# cell.net
KiCad netlist of a schematic drawn in EAGLE
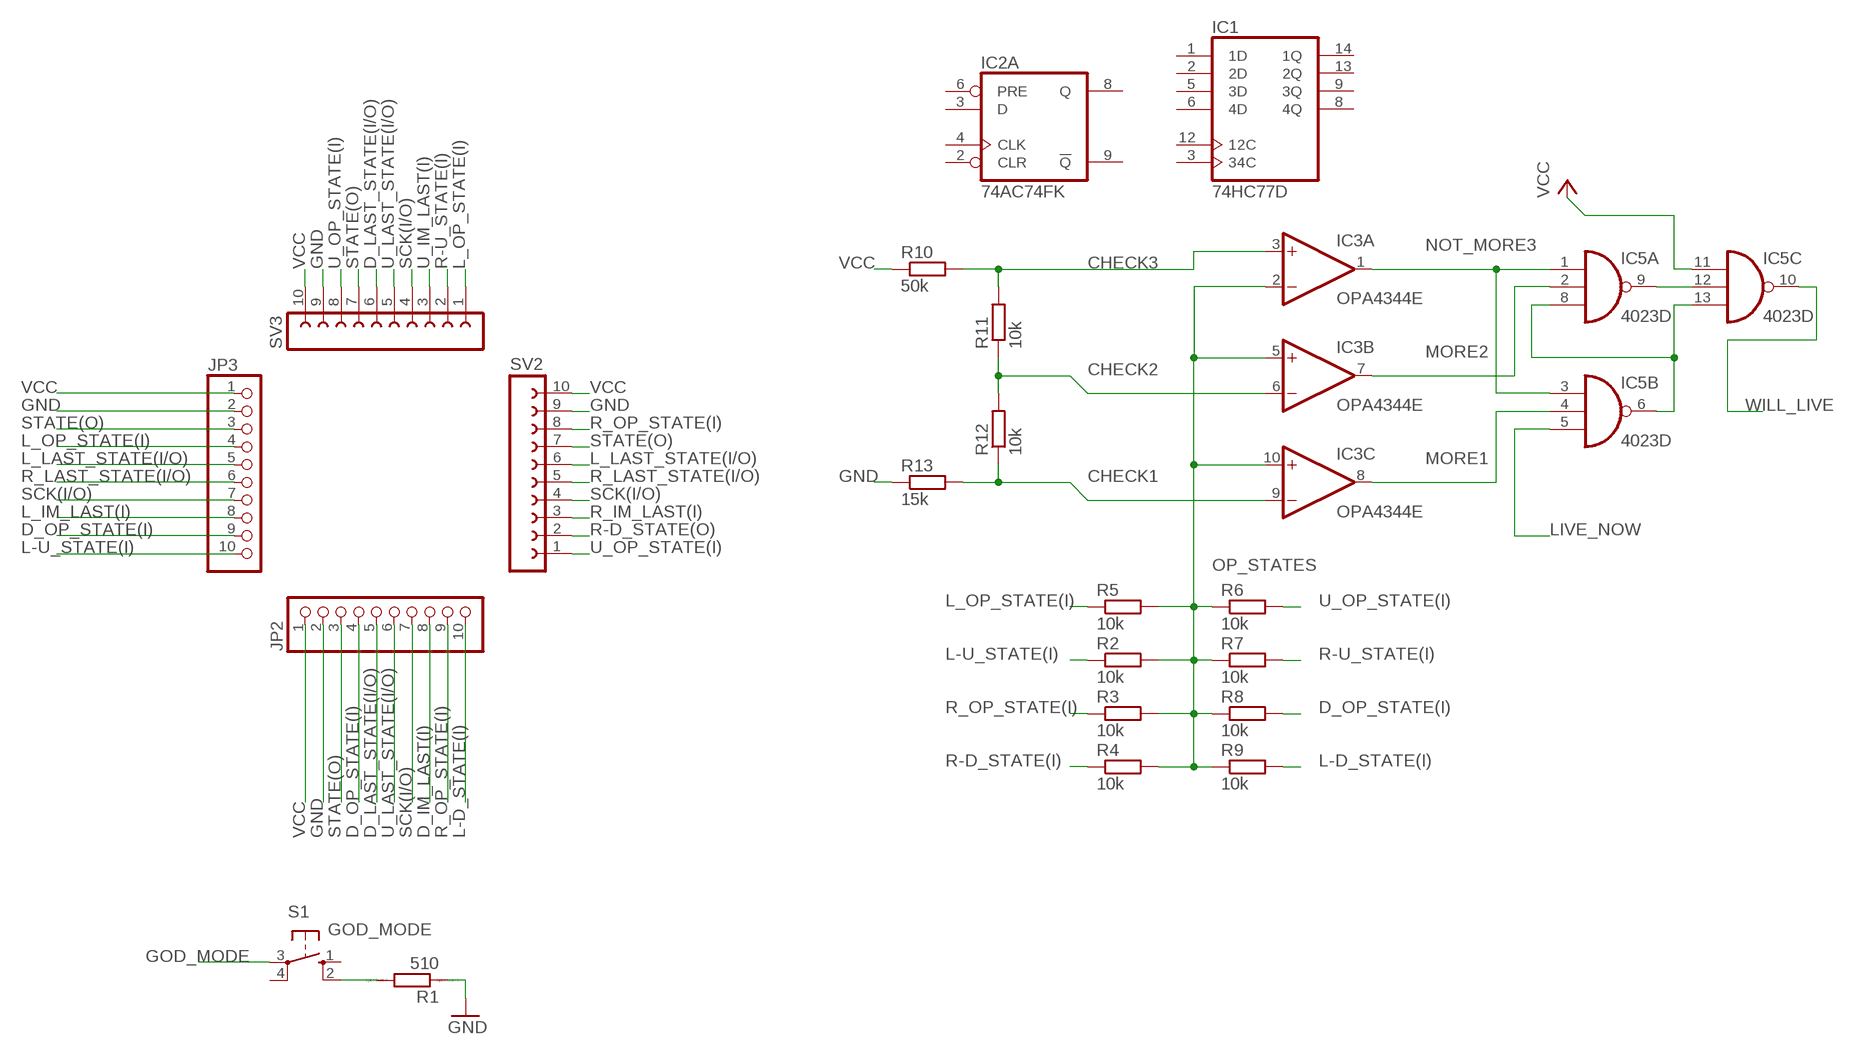
[diagram p0: schematic, sheet 1]

(export (version "E")
  (design (tool "Eeschema 10.0.6"))
  (components
    (comp (ref "IC1")
      (value "74HC77D")
      (footprint "eagle-import:SO14")
      (libsource (lib "eagle-import") (part "7477DHC"))
    )
    (comp (ref "IC2")
      (value "74AC74FK")
      (footprint "eagle-import:LCC20")
      (libsource (lib "eagle-import") (part "7474FKAC"))
    )
    (comp (ref "IC3")
      (value "OPA4344E")
      (footprint "eagle-import:TSSOP14")
      (libsource (lib "eagle-import") (part "OPA4E344"))
    )
    (comp (ref "IC5")
      (value "4023D")
      (footprint "eagle-import:SO14")
      (libsource (lib "eagle-import") (part "4023D"))
    )
    (comp (ref "JP2")
      (value "PINHD-1X10")
      (footprint "eagle-import:1X10")
      (libsource (lib "eagle-import") (part "PINHD-1X10"))
    )
    (comp (ref "JP3")
      (value "PINHD-1X10")
      (footprint "eagle-import:1X10")
      (libsource (lib "eagle-import") (part "PINHD-1X10"))
    )
    (comp (ref "R1")
      (value "510")
      (footprint "eagle-import:R0805")
      (libsource (lib "eagle-import") (part "R"))
    )
    (comp (ref "R2")
      (value "10k")
      (footprint "eagle-import:R0805")
      (libsource (lib "eagle-import") (part "R-EU_R0805"))
    )
    (comp (ref "R3")
      (value "10k")
      (footprint "eagle-import:R0805")
      (libsource (lib "eagle-import") (part "R-EU_R0805"))
    )
    (comp (ref "R4")
      (value "10k")
      (footprint "eagle-import:R0805")
      (libsource (lib "eagle-import") (part "R-EU_R0805"))
    )
    (comp (ref "R5")
      (value "10k")
      (footprint "eagle-import:R0805")
      (libsource (lib "eagle-import") (part "R-EU_R0805"))
    )
    (comp (ref "R6")
      (value "10k")
      (footprint "eagle-import:R0805")
      (libsource (lib "eagle-import") (part "R-EU_R0805"))
    )
    (comp (ref "R7")
      (value "10k")
      (footprint "eagle-import:R0805")
      (libsource (lib "eagle-import") (part "R-EU_R0805"))
    )
    (comp (ref "R8")
      (value "10k")
      (footprint "eagle-import:R0805")
      (libsource (lib "eagle-import") (part "R-EU_R0805"))
    )
    (comp (ref "R9")
      (value "10k")
      (footprint "eagle-import:R0805")
      (libsource (lib "eagle-import") (part "R-EU_R0805"))
    )
    (comp (ref "R10")
      (value "50k")
      (footprint "eagle-import:R0805")
      (libsource (lib "eagle-import") (part "R-EU_R0805"))
    )
    (comp (ref "R11")
      (value "10k")
      (footprint "eagle-import:R0805")
      (libsource (lib "eagle-import") (part "R-EU_R0805"))
    )
    (comp (ref "R12")
      (value "10k")
      (footprint "eagle-import:R0805")
      (libsource (lib "eagle-import") (part "R-EU_R0805"))
    )
    (comp (ref "R13")
      (value "15k")
      (footprint "eagle-import:R0805")
      (libsource (lib "eagle-import") (part "R-EU_R0805"))
    )
    (comp (ref "S1")
      (value "GOD_MODE")
      (footprint "eagle-import:B3F-10XX")
      (fields (field (name "MPN") "B3F-1000"))
      (libsource (lib "eagle-import") (part "10-XX"))
    )
    (comp (ref "SV2")
      (value "FE10W")
      (footprint "eagle-import:FE10W")
      (libsource (lib "eagle-import") (part "FE10W"))
    )
    (comp (ref "SV3")
      (value "FE10W")
      (footprint "eagle-import:FE10W")
      (libsource (lib "eagle-import") (part "FE10W"))
    )
  )
  (nets
    (net (code "1") (name "/CHECK1") (class "Default")
      (node (ref "IC3") (pin "9") (pinfunction "-IN_9") (pintype "input"))
      (node (ref "R12") (pin "1") (pinfunction "1_1") (pintype "passive"))
      (node (ref "R13") (pin "2") (pinfunction "2_2") (pintype "passive"))
    )
    (net (code "2") (name "/CHECK2") (class "Default")
      (node (ref "IC3") (pin "6") (pinfunction "-IN_6") (pintype "input"))
      (node (ref "R11") (pin "1") (pinfunction "1_1") (pintype "passive"))
      (node (ref "R12") (pin "2") (pinfunction "2_2") (pintype "passive"))
    )
    (net (code "3") (name "/CHECK3") (class "Default")
      (node (ref "IC3") (pin "3") (pinfunction "+IN_3") (pintype "input"))
      (node (ref "R10") (pin "2") (pinfunction "2_2") (pintype "passive"))
      (node (ref "R11") (pin "2") (pinfunction "2_2") (pintype "passive"))
    )
    (net (code "4") (name "/D_IM_LAST(I)") (class "Default")
      (node (ref "JP2") (pin "8") (pinfunction "8_8") (pintype "passive"))
    )
    (net (code "5") (name "/D_LAST_STATE(I{slash}O)") (class "Default")
      (node (ref "JP2") (pin "5") (pinfunction "5_5") (pintype "passive"))
      (node (ref "SV3") (pin "6") (pinfunction "6_6") (pintype "passive"))
    )
    (net (code "6") (name "/D_OP_STATE(I)") (class "Default")
      (node (ref "JP2") (pin "4") (pinfunction "4_4") (pintype "passive"))
      (node (ref "JP3") (pin "9") (pinfunction "9_9") (pintype "passive"))
      (node (ref "R8") (pin "2") (pinfunction "2_2") (pintype "passive"))
    )
    (net (code "7") (name "/GOD_MODE") (class "Default")
      (node (ref "S1") (pin "3") (pinfunction "P_3") (pintype "passive"))
    )
    (net (code "8") (name "/L-D_STATE(I)") (class "Default")
      (node (ref "JP2") (pin "10") (pinfunction "10_10") (pintype "passive"))
      (node (ref "R9") (pin "2") (pinfunction "2_2") (pintype "passive"))
    )
    (net (code "9") (name "/L-U_STATE(I)") (class "Default")
      (node (ref "JP3") (pin "10") (pinfunction "10_10") (pintype "passive"))
      (node (ref "R2") (pin "1") (pinfunction "1_1") (pintype "passive"))
    )
    (net (code "10") (name "/LIVE_NOW") (class "Default")
      (node (ref "IC5") (pin "5") (pinfunction "I2_5") (pintype "input"))
    )
    (net (code "11") (name "/L_IM_LAST(I)") (class "Default")
      (node (ref "JP3") (pin "8") (pinfunction "8_8") (pintype "passive"))
    )
    (net (code "12") (name "/L_LAST_STATE(I{slash}O)") (class "Default")
      (node (ref "JP3") (pin "5") (pinfunction "5_5") (pintype "passive"))
      (node (ref "SV2") (pin "6") (pinfunction "6_6") (pintype "passive"))
    )
    (net (code "13") (name "/L_OP_STATE(I)") (class "Default")
      (node (ref "JP3") (pin "4") (pinfunction "4_4") (pintype "passive"))
      (node (ref "R5") (pin "1") (pinfunction "1_1") (pintype "passive"))
      (node (ref "SV3") (pin "1") (pinfunction "1_1") (pintype "passive"))
    )
    (net (code "14") (name "/MORE1") (class "Default")
      (node (ref "IC3") (pin "8") (pinfunction "OUT_8") (pintype "output"))
      (node (ref "IC5") (pin "4") (pinfunction "I1_4") (pintype "input"))
    )
    (net (code "15") (name "/MORE2") (class "Default")
      (node (ref "IC3") (pin "7") (pinfunction "OUT_7") (pintype "output"))
      (node (ref "IC5") (pin "2") (pinfunction "I1_2") (pintype "input"))
    )
    (net (code "16") (name "/NOT_MORE3") (class "Default")
      (node (ref "IC3") (pin "1") (pinfunction "OUT_1") (pintype "output"))
      (node (ref "IC5") (pin "1") (pinfunction "I0_1") (pintype "input"))
      (node (ref "IC5") (pin "3") (pinfunction "I0_3") (pintype "input"))
    )
    (net (code "17") (name "/OP_STATES") (class "Default")
      (node (ref "IC3") (pin "10") (pinfunction "+IN_10") (pintype "input"))
      (node (ref "IC3") (pin "2") (pinfunction "-IN_2") (pintype "input"))
      (node (ref "IC3") (pin "5") (pinfunction "+IN_5") (pintype "input"))
      (node (ref "R2") (pin "2") (pinfunction "2_2") (pintype "passive"))
      (node (ref "R3") (pin "2") (pinfunction "2_2") (pintype "passive"))
      (node (ref "R4") (pin "2") (pinfunction "2_2") (pintype "passive"))
      (node (ref "R5") (pin "2") (pinfunction "2_2") (pintype "passive"))
      (node (ref "R6") (pin "1") (pinfunction "1_1") (pintype "passive"))
      (node (ref "R7") (pin "1") (pinfunction "1_1") (pintype "passive"))
      (node (ref "R8") (pin "1") (pinfunction "1_1") (pintype "passive"))
      (node (ref "R9") (pin "1") (pinfunction "1_1") (pintype "passive"))
    )
    (net (code "18") (name "/R-D_STATE(I)") (class "Default")
      (node (ref "R4") (pin "1") (pinfunction "1_1") (pintype "passive"))
    )
    (net (code "19") (name "/R-D_STATE(O)") (class "Default")
      (node (ref "SV2") (pin "2") (pinfunction "2_2") (pintype "passive"))
    )
    (net (code "20") (name "/R-U_STATE(I)") (class "Default")
      (node (ref "R7") (pin "2") (pinfunction "2_2") (pintype "passive"))
      (node (ref "SV3") (pin "2") (pinfunction "2_2") (pintype "passive"))
    )
    (net (code "21") (name "/R_IM_LAST(I)") (class "Default")
      (node (ref "SV2") (pin "3") (pinfunction "3_3") (pintype "passive"))
    )
    (net (code "22") (name "/R_LAST_STATE(I{slash}O)") (class "Default")
      (node (ref "JP3") (pin "6") (pinfunction "6_6") (pintype "passive"))
      (node (ref "SV2") (pin "5") (pinfunction "5_5") (pintype "passive"))
    )
    (net (code "23") (name "/R_OP_STATE(I)") (class "Default")
      (node (ref "JP2") (pin "9") (pinfunction "9_9") (pintype "passive"))
      (node (ref "R3") (pin "1") (pinfunction "1_1") (pintype "passive"))
      (node (ref "SV2") (pin "8") (pinfunction "8_8") (pintype "passive"))
    )
    (net (code "24") (name "/SCK(I{slash}O)") (class "Default")
      (node (ref "JP2") (pin "7") (pinfunction "7_7") (pintype "passive"))
      (node (ref "JP3") (pin "7") (pinfunction "7_7") (pintype "passive"))
      (node (ref "SV2") (pin "4") (pinfunction "4_4") (pintype "passive"))
      (node (ref "SV3") (pin "4") (pinfunction "4_4") (pintype "passive"))
    )
    (net (code "25") (name "/STATE(O)") (class "Default")
      (node (ref "JP2") (pin "3") (pinfunction "3_3") (pintype "passive"))
      (node (ref "JP3") (pin "3") (pinfunction "3_3") (pintype "passive"))
      (node (ref "SV2") (pin "7") (pinfunction "7_7") (pintype "passive"))
      (node (ref "SV3") (pin "7") (pinfunction "7_7") (pintype "passive"))
    )
    (net (code "26") (name "/U_IM_LAST(I)") (class "Default")
      (node (ref "SV3") (pin "3") (pinfunction "3_3") (pintype "passive"))
    )
    (net (code "27") (name "/U_LAST_STATE(I{slash}O)") (class "Default")
      (node (ref "JP2") (pin "6") (pinfunction "6_6") (pintype "passive"))
      (node (ref "SV3") (pin "5") (pinfunction "5_5") (pintype "passive"))
    )
    (net (code "28") (name "/U_OP_STATE(I)") (class "Default")
      (node (ref "R6") (pin "2") (pinfunction "2_2") (pintype "passive"))
      (node (ref "SV2") (pin "1") (pinfunction "1_1") (pintype "passive"))
      (node (ref "SV3") (pin "8") (pinfunction "8_8") (pintype "passive"))
    )
    (net (code "29") (name "/WILL_LIVE") (class "Default")
      (node (ref "IC5") (pin "10") (pinfunction "O_10") (pintype "output"))
    )
    (net (code "30") (name "GND") (class "Default")
      (node (ref "JP2") (pin "2") (pinfunction "2_2") (pintype "passive"))
      (node (ref "JP3") (pin "2") (pinfunction "2_2") (pintype "passive"))
      (node (ref "R1") (pin "1") (pinfunction "1_1") (pintype "passive"))
      (node (ref "R13") (pin "1") (pinfunction "1_1") (pintype "passive"))
      (node (ref "SV2") (pin "9") (pinfunction "9_9") (pintype "passive"))
      (node (ref "SV3") (pin "9") (pinfunction "9_9") (pintype "passive"))
    )
    (net (code "31") (name "Net-(IC5A-I2)") (class "Default")
      (node (ref "IC5") (pin "13") (pinfunction "I2_13") (pintype "input"))
      (node (ref "IC5") (pin "6") (pinfunction "O_6") (pintype "output"))
      (node (ref "IC5") (pin "8") (pinfunction "I2_8") (pintype "input"))
    )
    (net (code "32") (name "Net-(IC5A-O)") (class "Default")
      (node (ref "IC5") (pin "12") (pinfunction "I1_12") (pintype "input"))
      (node (ref "IC5") (pin "9") (pinfunction "O_9") (pintype "output"))
    )
    (net (code "33") (name "Net-(S1-S1)") (class "Default")
      (node (ref "R1") (pin "2") (pinfunction "2_2") (pintype "passive"))
      (node (ref "S1") (pin "2") (pinfunction "S1_2") (pintype "passive"))
    )
    (net (code "34") (name "VCC") (class "Default")
      (node (ref "IC5") (pin "11") (pinfunction "I0_11") (pintype "input"))
      (node (ref "JP2") (pin "1") (pinfunction "1_1") (pintype "passive"))
      (node (ref "JP3") (pin "1") (pinfunction "1_1") (pintype "passive"))
      (node (ref "R10") (pin "1") (pinfunction "1_1") (pintype "passive"))
      (node (ref "SV2") (pin "10") (pinfunction "10_10") (pintype "passive"))
      (node (ref "SV3") (pin "10") (pinfunction "10_10") (pintype "passive"))
    )
    (net (code "35") (name "unconnected-(IC1A-1D-Pad1)") (class "Default")
      (node (ref "IC1") (pin "1") (pinfunction "1D_1") (pintype "input"))
    )
    (net (code "36") (name "unconnected-(IC1A-1Q-Pad14)") (class "Default")
      (node (ref "IC1") (pin "14") (pinfunction "1Q_14") (pintype "output"))
    )
    (net (code "37") (name "unconnected-(IC1A-2D-Pad2)") (class "Default")
      (node (ref "IC1") (pin "2") (pinfunction "2D_2") (pintype "input"))
    )
    (net (code "38") (name "unconnected-(IC1A-2Q-Pad13)") (class "Default")
      (node (ref "IC1") (pin "13") (pinfunction "2Q_13") (pintype "output"))
    )
    (net (code "39") (name "unconnected-(IC1A-3D-Pad5)") (class "Default")
      (node (ref "IC1") (pin "5") (pinfunction "3D_5") (pintype "input"))
    )
    (net (code "40") (name "unconnected-(IC1A-3Q-Pad9)") (class "Default")
      (node (ref "IC1") (pin "9") (pinfunction "3Q_9") (pintype "output"))
    )
    (net (code "41") (name "unconnected-(IC1A-4D-Pad6)") (class "Default")
      (node (ref "IC1") (pin "6") (pinfunction "4D_6") (pintype "input"))
    )
    (net (code "42") (name "unconnected-(IC1A-4Q-Pad8)") (class "Default")
      (node (ref "IC1") (pin "8") (pinfunction "4Q_8") (pintype "output"))
    )
    (net (code "43") (name "unconnected-(IC1A-12C-Pad12)") (class "Default")
      (node (ref "IC1") (pin "12") (pinfunction "12C_12") (pintype "input"))
    )
    (net (code "44") (name "unconnected-(IC1A-34C-Pad3)") (class "Default")
      (node (ref "IC1") (pin "3") (pinfunction "34C_3") (pintype "input"))
    )
    (net (code "45") (name "unconnected-(IC2A-CLK-Pad4)") (class "Default")
      (node (ref "IC2") (pin "4") (pinfunction "CLK_4") (pintype "input"))
    )
    (net (code "46") (name "unconnected-(IC2A-CLR-Pad2)") (class "Default")
      (node (ref "IC2") (pin "2") (pinfunction "CLR_2") (pintype "input"))
    )
    (net (code "47") (name "unconnected-(IC2A-D-Pad3)") (class "Default")
      (node (ref "IC2") (pin "3") (pinfunction "D_3") (pintype "input"))
    )
    (net (code "48") (name "unconnected-(IC2A-PRE-Pad6)") (class "Default")
      (node (ref "IC2") (pin "6") (pinfunction "PRE_6") (pintype "input"))
    )
    (net (code "49") (name "unconnected-(IC2A-Q-Pad8)") (class "Default")
      (node (ref "IC2") (pin "8") (pinfunction "Q_8") (pintype "output"))
    )
    (net (code "50") (name "unconnected-(IC2A-~{Q}-Pad9)") (class "Default")
      (node (ref "IC2") (pin "9") (pinfunction "~{Q}_9") (pintype "output"))
    )
    (net (code "51") (name "unconnected-(S1-P1-Pad4)") (class "Default")
      (node (ref "S1") (pin "4") (pinfunction "P1_4") (pintype "passive"))
    )
    (net (code "52") (name "unconnected-(S1-S-Pad1)") (class "Default")
      (node (ref "S1") (pin "1") (pinfunction "S_1") (pintype "passive"))
    )
  )
)
